# 120VAC.net
KiCad netlist of a schematic drawn in EAGLE
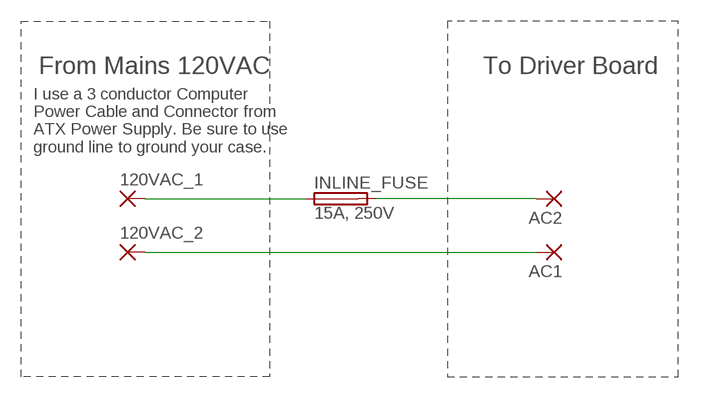
[diagram p0: schematic, sheet 1]

(export (version "E")
  (design (tool "Eeschema 10.0.6"))
  (components
    (comp (ref "120VAC_1")
      (value "1,6/0,9")
      (footprint "eagle-import:1,6_0,9")
      (libsource (lib "eagle-import") (part "1,6/0,9"))
    )
    (comp (ref "120VAC_2")
      (value "1,6/0,9")
      (footprint "eagle-import:1,6_0,9")
      (libsource (lib "eagle-import") (part "1,6/0,9"))
    )
    (comp (ref "AC1")
      (value "1,6/0,9")
      (footprint "eagle-import:1,6_0,9")
      (libsource (lib "eagle-import") (part "1,6/0,9"))
    )
    (comp (ref "AC2")
      (value "1,6/0,9")
      (footprint "eagle-import:1,6_0,9")
      (libsource (lib "eagle-import") (part "1,6/0,9"))
    )
    (comp (ref "INLINE_FUSE")
      (value "15A, 250V")
      (footprint "eagle-import:SH25")
      (fields (field (name "MF") "SCHURTER") (field (name "MPN") "0031.8211"))
      (libsource (lib "eagle-import") (part "SH25"))
    )
  )
  (nets
    (net (code "1") (name "Net-(120VAC_1-P)") (class "Default")
      (node (ref "120VAC_1") (pin "1") (pinfunction "P_1") (pintype "passive"))
      (node (ref "INLINE_FUSE") (pin "1") (pinfunction "1_1") (pintype "passive"))
    )
    (net (code "2") (name "Net-(120VAC_2-P)") (class "Default")
      (node (ref "120VAC_2") (pin "1") (pinfunction "P_1") (pintype "passive"))
      (node (ref "AC1") (pin "1") (pinfunction "P_1") (pintype "passive"))
    )
    (net (code "3") (name "Net-(AC2-P)") (class "Default")
      (node (ref "AC2") (pin "1") (pinfunction "P_1") (pintype "passive"))
      (node (ref "INLINE_FUSE") (pin "2") (pinfunction "2_2") (pintype "passive"))
    )
  )
)
